# RDF4463_Beacon_v1.net
KiCad netlist of a schematic drawn in EAGLE
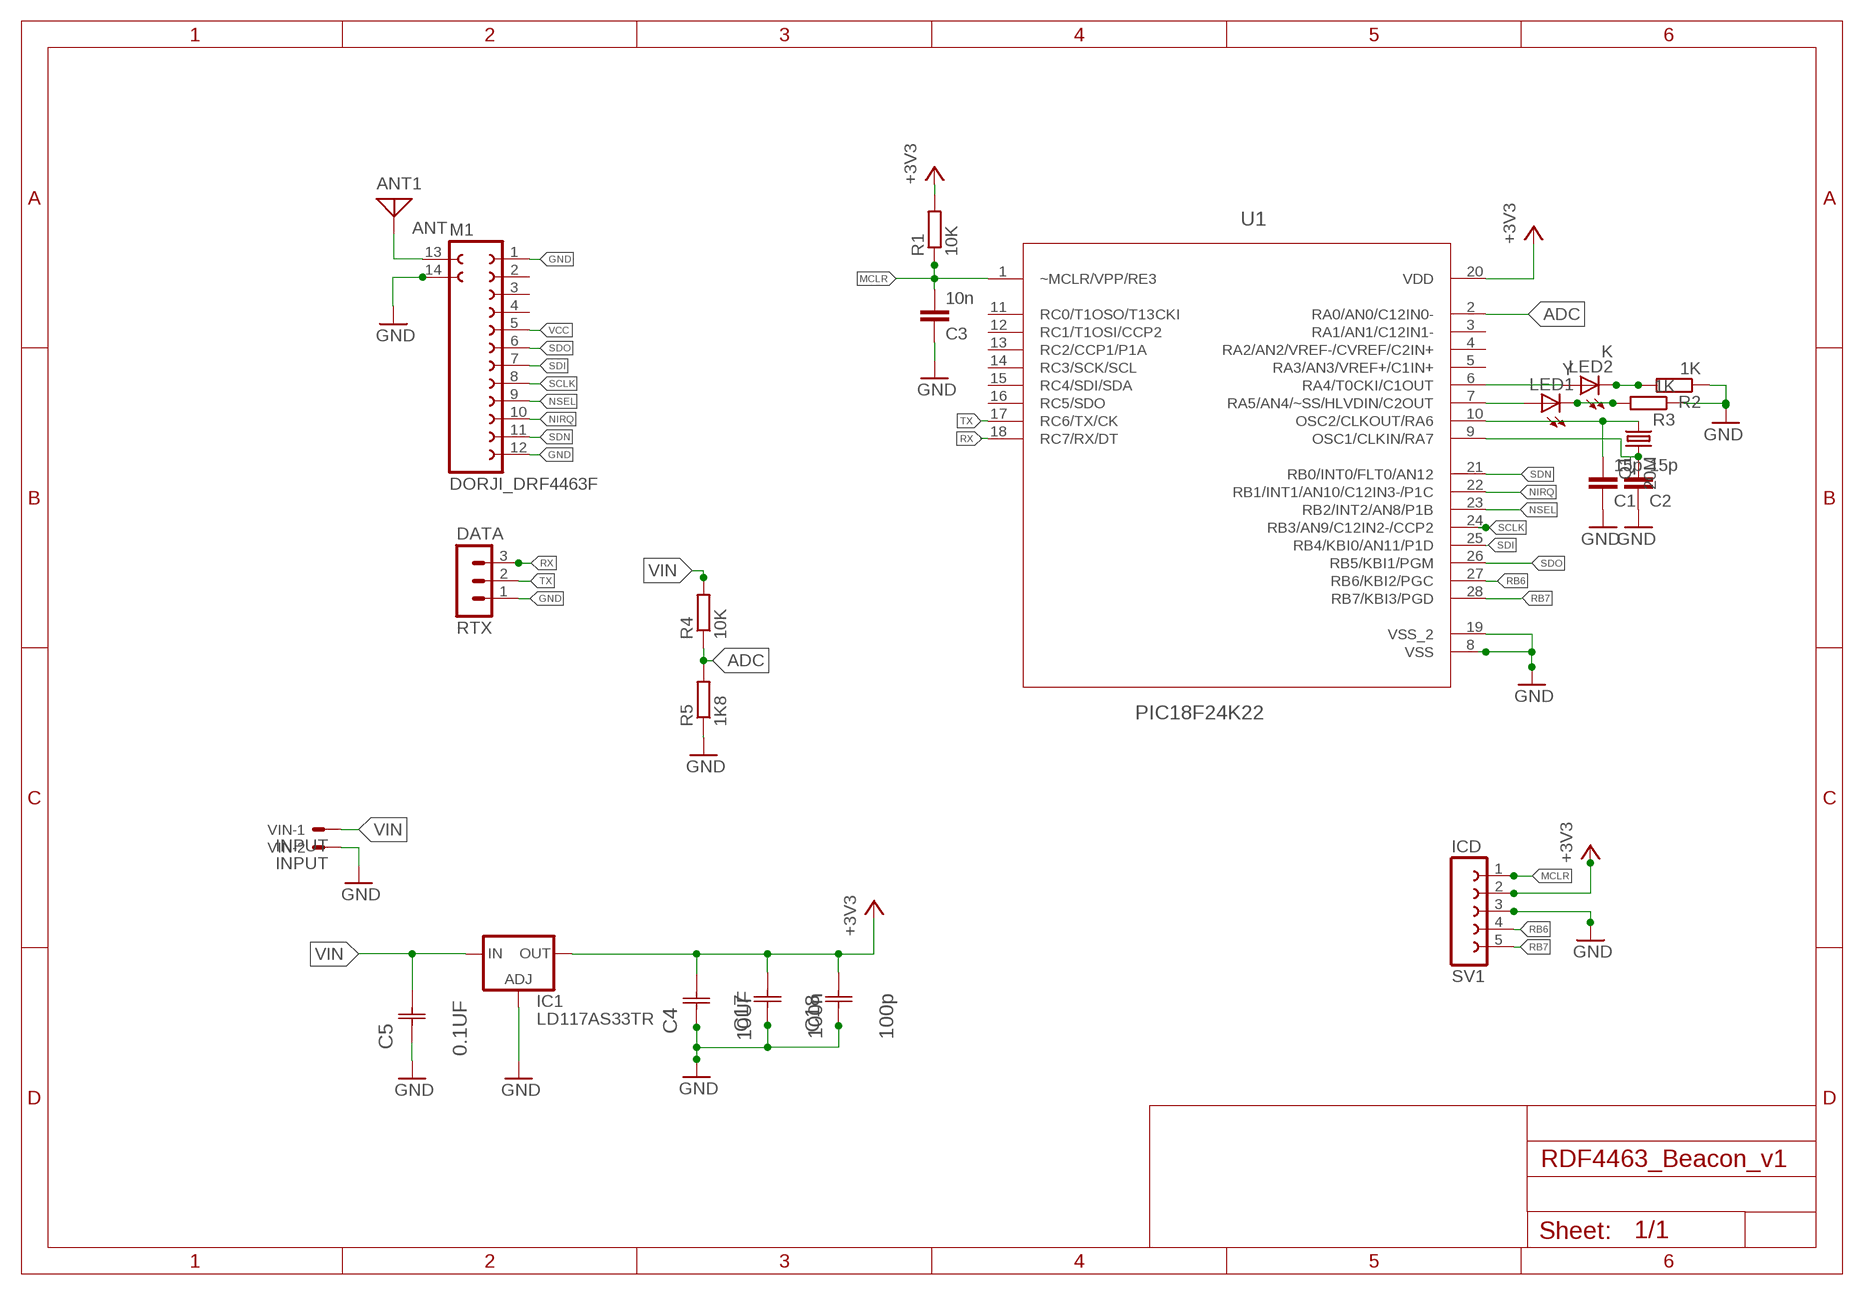
[diagram p0: schematic, sheet 1]

(export (version "E")
  (design (tool "Eeschema 10.0.6"))
  (components
    (comp (ref "ANT1")
      (value "ANT")
      (footprint "eagle-import:PAD-01")
      (libsource (lib "eagle-import") (part "ANTENNA"))
    )
    (comp (ref "C1")
      (value "15p")
      (footprint "eagle-import:C0805")
      (libsource (lib "eagle-import") (part "C-EUC0805"))
    )
    (comp (ref "C2")
      (value "15p")
      (footprint "eagle-import:C0805")
      (libsource (lib "eagle-import") (part "C-EUC0805"))
    )
    (comp (ref "C3")
      (value "10n")
      (footprint "eagle-import:C0805")
      (libsource (lib "eagle-import") (part "C-EUC0805"))
    )
    (comp (ref "C4")
      (value "10UF")
      (footprint "eagle-import:CAPC2013X140N")
      (fields (field (name "MPN") "0805YD106MAT2A") (field (name "TOLERANCE") "±20%"))
      (libsource (lib "eagle-import") (part "0805YD106MAT2A"))
    )
    (comp (ref "C5")
      (value "0.1UF")
      (footprint "eagle-import:CAPC2012X94N")
      (fields (field (name "MPN") "0805ZC104MAT2A") (field (name "TOLERANCE") "±20%"))
      (libsource (lib "eagle-import") (part "0805ZC104MAT2A"))
    )
    (comp (ref "C17")
      (value "100n")
      (footprint "eagle-import:CAPC2013X140N")
      (fields (field (name "MPN") "0805YD106MAT2A") (field (name "TOLERANCE") "±20%"))
      (libsource (lib "eagle-import") (part "0805YD106MAT2A"))
    )
    (comp (ref "C18")
      (value "100p")
      (footprint "eagle-import:CAPC2013X140N")
      (fields (field (name "MPN") "0805YD106MAT2A") (field (name "TOLERANCE") "±20%"))
      (libsource (lib "eagle-import") (part "0805YD106MAT2A"))
    )
    (comp (ref "DATA")
      (value "RTX")
      (footprint "eagle-import:MA03-1")
      (libsource (lib "eagle-import") (part "MA03-1"))
    )
    (comp (ref "IC1")
      (value "LD117AS33TR")
      (footprint "eagle-import:SOT223")
      (libsource (lib "eagle-import") (part "LD117A?S33TR"))
    )
    (comp (ref "LED1")
      (value "Y")
      (footprint "eagle-import:SML0805")
      (libsource (lib "eagle-import") (part "LEDSML0805"))
    )
    (comp (ref "LED2")
      (value "K")
      (footprint "eagle-import:SML0805")
      (libsource (lib "eagle-import") (part "LEDSML0805"))
    )
    (comp (ref "M1")
      (value "DORJI_DRF4463F")
      (footprint "eagle-import:DORJI_DRF4463F")
      (libsource (lib "eagle-import") (part "DORJI_DRF4463F"))
    )
    (comp (ref "Q1")
      (value "20M")
      (footprint "eagle-import:SM49")
      (libsource (lib "eagle-import") (part "CRYSTALSM49"))
    )
    (comp (ref "R1")
      (value "10K")
      (footprint "eagle-import:R0805")
      (libsource (lib "eagle-import") (part "R-EU_R0805"))
    )
    (comp (ref "R2")
      (value "1K")
      (footprint "eagle-import:R0805")
      (libsource (lib "eagle-import") (part "R-EU_R0805"))
    )
    (comp (ref "R3")
      (value "1K")
      (footprint "eagle-import:R0805")
      (libsource (lib "eagle-import") (part "R-EU_R0805"))
    )
    (comp (ref "R4")
      (value "10K")
      (footprint "eagle-import:R0805")
      (libsource (lib "eagle-import") (part "R-EU_R0805"))
    )
    (comp (ref "R5")
      (value "1K8")
      (footprint "eagle-import:R0805")
      (libsource (lib "eagle-import") (part "R-EU_R0805"))
    )
    (comp (ref "SV1")
      (value "ICD")
      (footprint "eagle-import:FE05-1")
      (libsource (lib "eagle-import") (part "FE05-1"))
    )
    (comp (ref "U1")
      (value "PIC18F24K22")
      (footprint "eagle-import:SSPO28")
      (libsource (lib "eagle-import") (part "PIC18F24K22"))
    )
    (comp (ref "VIN")
      (value "INPUT")
      (footprint "eagle-import:KK-156-2")
      (libsource (lib "eagle-import") (part "KK-156-2"))
    )
  )
  (nets
    (net (code "1") (name "ADC") (class "Default")
      (node (ref "R4") (pin "1") (pinfunction "1_1") (pintype "passive"))
      (node (ref "R5") (pin "2") (pinfunction "2_2") (pintype "passive"))
      (node (ref "U1") (pin "2") (pinfunction "RA0/AN0/C12IN0-_2") (pintype "bidirectional"))
    )
    (net (code "2") (name "GND") (class "Default")
      (node (ref "C1") (pin "1") (pinfunction "1_1") (pintype "passive"))
      (node (ref "C17") (pin "1") (pinfunction "C1_1") (pintype "passive"))
      (node (ref "C18") (pin "1") (pinfunction "C1_1") (pintype "passive"))
      (node (ref "C2") (pin "1") (pinfunction "1_1") (pintype "passive"))
      (node (ref "C3") (pin "1") (pinfunction "1_1") (pintype "passive"))
      (node (ref "C4") (pin "1") (pinfunction "C1_1") (pintype "passive"))
      (node (ref "C5") (pin "1") (pinfunction "C1_1") (pintype "passive"))
      (node (ref "DATA") (pin "1") (pinfunction "1_1") (pintype "passive"))
      (node (ref "IC1") (pin "1") (pinfunction "ADJ_1") (pintype "input"))
      (node (ref "M1") (pin "1") (pinfunction "1_1") (pintype "passive"))
      (node (ref "M1") (pin "12") (pinfunction "12_12") (pintype "passive"))
      (node (ref "M1") (pin "14") (pinfunction "14_14") (pintype "passive"))
      (node (ref "R2") (pin "1") (pinfunction "1_1") (pintype "passive"))
      (node (ref "R3") (pin "1") (pinfunction "1_1") (pintype "passive"))
      (node (ref "R5") (pin "1") (pinfunction "1_1") (pintype "passive"))
      (node (ref "SV1") (pin "3") (pinfunction "3_3") (pintype "passive"))
      (node (ref "U1") (pin "19") (pinfunction "VSS_2_19") (pintype "power_in"))
      (node (ref "U1") (pin "8") (pinfunction "VSS_8") (pintype "power_in"))
      (node (ref "VIN") (pin "2") (pinfunction "S_2") (pintype "passive"))
    )
    (net (code "3") (name "MCLR") (class "Default")
      (node (ref "C3") (pin "2") (pinfunction "2_2") (pintype "passive"))
      (node (ref "R1") (pin "1") (pinfunction "1_1") (pintype "passive"))
      (node (ref "SV1") (pin "1") (pinfunction "1_1") (pintype "passive"))
      (node (ref "U1") (pin "1") (pinfunction "~{MCLR/VPP/RE3}_1") (pintype "bidirectional"))
    )
    (net (code "4") (name "NIRQ") (class "Default")
      (node (ref "M1") (pin "10") (pinfunction "10_10") (pintype "passive"))
      (node (ref "U1") (pin "22") (pinfunction "RB1/INT1/AN10/C12IN3-/P1C_22") (pintype "bidirectional"))
    )
    (net (code "5") (name "NSEL") (class "Default")
      (node (ref "M1") (pin "9") (pinfunction "9_9") (pintype "passive"))
      (node (ref "U1") (pin "23") (pinfunction "RB2/INT2/AN8/P1B_23") (pintype "bidirectional"))
    )
    (net (code "6") (name "Net-(ANT1-Pad1)") (class "Default")
      (node (ref "ANT1") (pin "1") (pinfunction "1_1") (pintype "output"))
      (node (ref "M1") (pin "13") (pinfunction "13_13") (pintype "passive"))
    )
    (net (code "7") (name "Net-(LED1-PadC)") (class "Default")
      (node (ref "LED1") (pin "C") (pinfunction "C_C") (pintype "passive"))
      (node (ref "R3") (pin "2") (pinfunction "2_2") (pintype "passive"))
    )
    (net (code "8") (name "Net-(LED2-PadC)") (class "Default")
      (node (ref "LED2") (pin "C") (pinfunction "C_C") (pintype "passive"))
      (node (ref "R2") (pin "2") (pinfunction "2_2") (pintype "passive"))
    )
    (net (code "9") (name "Net-(U1-OSC1{slash}CLKIN{slash}RA7)") (class "Default")
      (node (ref "C2") (pin "2") (pinfunction "2_2") (pintype "passive"))
      (node (ref "Q1") (pin "2") (pinfunction "2_2") (pintype "passive"))
      (node (ref "U1") (pin "9") (pinfunction "OSC1/CLKIN/RA7_9") (pintype "bidirectional"))
    )
    (net (code "10") (name "Net-(U1-OSC2{slash}CLKOUT{slash}RA6)") (class "Default")
      (node (ref "C1") (pin "2") (pinfunction "2_2") (pintype "passive"))
      (node (ref "Q1") (pin "1") (pinfunction "1_1") (pintype "passive"))
      (node (ref "U1") (pin "10") (pinfunction "OSC2/CLKOUT/RA6_10") (pintype "bidirectional"))
    )
    (net (code "11") (name "Net-(U1-RA4{slash}T0CKI{slash}C1OUT)") (class "Default")
      (node (ref "LED2") (pin "A") (pinfunction "A_A") (pintype "passive"))
      (node (ref "U1") (pin "6") (pinfunction "RA4/T0CKI/C1OUT_6") (pintype "bidirectional"))
    )
    (net (code "12") (name "Net-(U1-RA5{slash}AN4{slash}~{SS{slash}HLVDIN{slash}C2OUT})") (class "Default")
      (node (ref "LED1") (pin "A") (pinfunction "A_A") (pintype "passive"))
      (node (ref "U1") (pin "7") (pinfunction "RA5/AN4/~{SS/HLVDIN/C2OUT}_7") (pintype "bidirectional"))
    )
    (net (code "13") (name "RB6") (class "Default")
      (node (ref "SV1") (pin "4") (pinfunction "4_4") (pintype "passive"))
      (node (ref "U1") (pin "27") (pinfunction "RB6/KBI2/PGC_27") (pintype "bidirectional"))
    )
    (net (code "14") (name "RB7") (class "Default")
      (node (ref "SV1") (pin "5") (pinfunction "5_5") (pintype "passive"))
      (node (ref "U1") (pin "28") (pinfunction "RB7/KBI3/PGD_28") (pintype "bidirectional"))
    )
    (net (code "15") (name "RX") (class "Default")
      (node (ref "DATA") (pin "3") (pinfunction "3_3") (pintype "passive"))
      (node (ref "U1") (pin "18") (pinfunction "RC7/RX/DT_18") (pintype "bidirectional"))
    )
    (net (code "16") (name "SCLK") (class "Default")
      (node (ref "M1") (pin "8") (pinfunction "8_8") (pintype "passive"))
      (node (ref "U1") (pin "24") (pinfunction "RB3/AN9/C12IN2-/CCP2_24") (pintype "bidirectional"))
    )
    (net (code "17") (name "SDI") (class "Default")
      (node (ref "M1") (pin "7") (pinfunction "7_7") (pintype "passive"))
      (node (ref "U1") (pin "25") (pinfunction "RB4/KBI0/AN11/P1D_25") (pintype "bidirectional"))
    )
    (net (code "18") (name "SDN") (class "Default")
      (node (ref "M1") (pin "11") (pinfunction "11_11") (pintype "passive"))
      (node (ref "U1") (pin "21") (pinfunction "RB0/INT0/FLT0/AN12_21") (pintype "bidirectional"))
    )
    (net (code "19") (name "SDO") (class "Default")
      (node (ref "M1") (pin "6") (pinfunction "6_6") (pintype "passive"))
      (node (ref "U1") (pin "26") (pinfunction "RB5/KBI1/PGM_26") (pintype "bidirectional"))
    )
    (net (code "20") (name "TX") (class "Default")
      (node (ref "DATA") (pin "2") (pinfunction "2_2") (pintype "passive"))
      (node (ref "U1") (pin "17") (pinfunction "RC6/TX/CK_17") (pintype "bidirectional"))
    )
    (net (code "21") (name "VCC") (class "Default")
      (node (ref "C17") (pin "2") (pinfunction "C2_2") (pintype "passive"))
      (node (ref "C18") (pin "2") (pinfunction "C2_2") (pintype "passive"))
      (node (ref "C4") (pin "2") (pinfunction "C2_2") (pintype "passive"))
      (node (ref "IC1") (pin "4") (pinfunction "OUT_4") (pintype "passive"))
      (node (ref "M1") (pin "5") (pinfunction "5_5") (pintype "passive"))
      (node (ref "R1") (pin "2") (pinfunction "2_2") (pintype "passive"))
      (node (ref "SV1") (pin "2") (pinfunction "2_2") (pintype "passive"))
      (node (ref "U1") (pin "20") (pinfunction "VDD_20") (pintype "power_in"))
    )
    (net (code "22") (name "VIN") (class "Default")
      (node (ref "C5") (pin "2") (pinfunction "C2_2") (pintype "passive"))
      (node (ref "IC1") (pin "3") (pinfunction "IN_3") (pintype "input"))
      (node (ref "R4") (pin "2") (pinfunction "2_2") (pintype "passive"))
      (node (ref "VIN") (pin "1") (pinfunction "S_1") (pintype "passive"))
    )
    (net (code "23") (name "unconnected-(M1-Pad2)") (class "Default")
      (node (ref "M1") (pin "2") (pinfunction "2_2") (pintype "passive"))
    )
    (net (code "24") (name "unconnected-(M1-Pad3)") (class "Default")
      (node (ref "M1") (pin "3") (pinfunction "3_3") (pintype "passive"))
    )
    (net (code "25") (name "unconnected-(M1-Pad4)") (class "Default")
      (node (ref "M1") (pin "4") (pinfunction "4_4") (pintype "passive"))
    )
    (net (code "26") (name "unconnected-(U1-RA1{slash}AN1{slash}C12IN1--Pad3)") (class "Default")
      (node (ref "U1") (pin "3") (pinfunction "RA1/AN1/C12IN1-_3") (pintype "bidirectional"))
    )
    (net (code "27") (name "unconnected-(U1-RA2{slash}AN2{slash}VREF-{slash}CVREF{slash}C2IN+-Pad4)") (class "Default")
      (node (ref "U1") (pin "4") (pinfunction "RA2/AN2/VREF-/CVREF/C2IN+_4") (pintype "bidirectional"))
    )
    (net (code "28") (name "unconnected-(U1-RA3{slash}AN3{slash}VREF+{slash}C1IN+-Pad5)") (class "Default")
      (node (ref "U1") (pin "5") (pinfunction "RA3/AN3/VREF+/C1IN+_5") (pintype "bidirectional"))
    )
    (net (code "29") (name "unconnected-(U1-RC0{slash}T1OSO{slash}T13CKI-Pad11)") (class "Default")
      (node (ref "U1") (pin "11") (pinfunction "RC0/T1OSO/T13CKI_11") (pintype "bidirectional"))
    )
    (net (code "30") (name "unconnected-(U1-RC1{slash}T1OSI{slash}CCP2-Pad12)") (class "Default")
      (node (ref "U1") (pin "12") (pinfunction "RC1/T1OSI/CCP2_12") (pintype "bidirectional"))
    )
    (net (code "31") (name "unconnected-(U1-RC2{slash}CCP1{slash}P1A-Pad13)") (class "Default")
      (node (ref "U1") (pin "13") (pinfunction "RC2/CCP1/P1A_13") (pintype "bidirectional"))
    )
    (net (code "32") (name "unconnected-(U1-RC3{slash}SCK{slash}SCL-Pad14)") (class "Default")
      (node (ref "U1") (pin "14") (pinfunction "RC3/SCK/SCL_14") (pintype "bidirectional"))
    )
    (net (code "33") (name "unconnected-(U1-RC4{slash}SDI{slash}SDA-Pad15)") (class "Default")
      (node (ref "U1") (pin "15") (pinfunction "RC4/SDI/SDA_15") (pintype "bidirectional"))
    )
    (net (code "34") (name "unconnected-(U1-RC5{slash}SDO-Pad16)") (class "Default")
      (node (ref "U1") (pin "16") (pinfunction "RC5/SDO_16") (pintype "bidirectional"))
    )
  )
)
